# IDE_44m_to_44m.net
KiCad netlist of a schematic drawn in Altium Designer
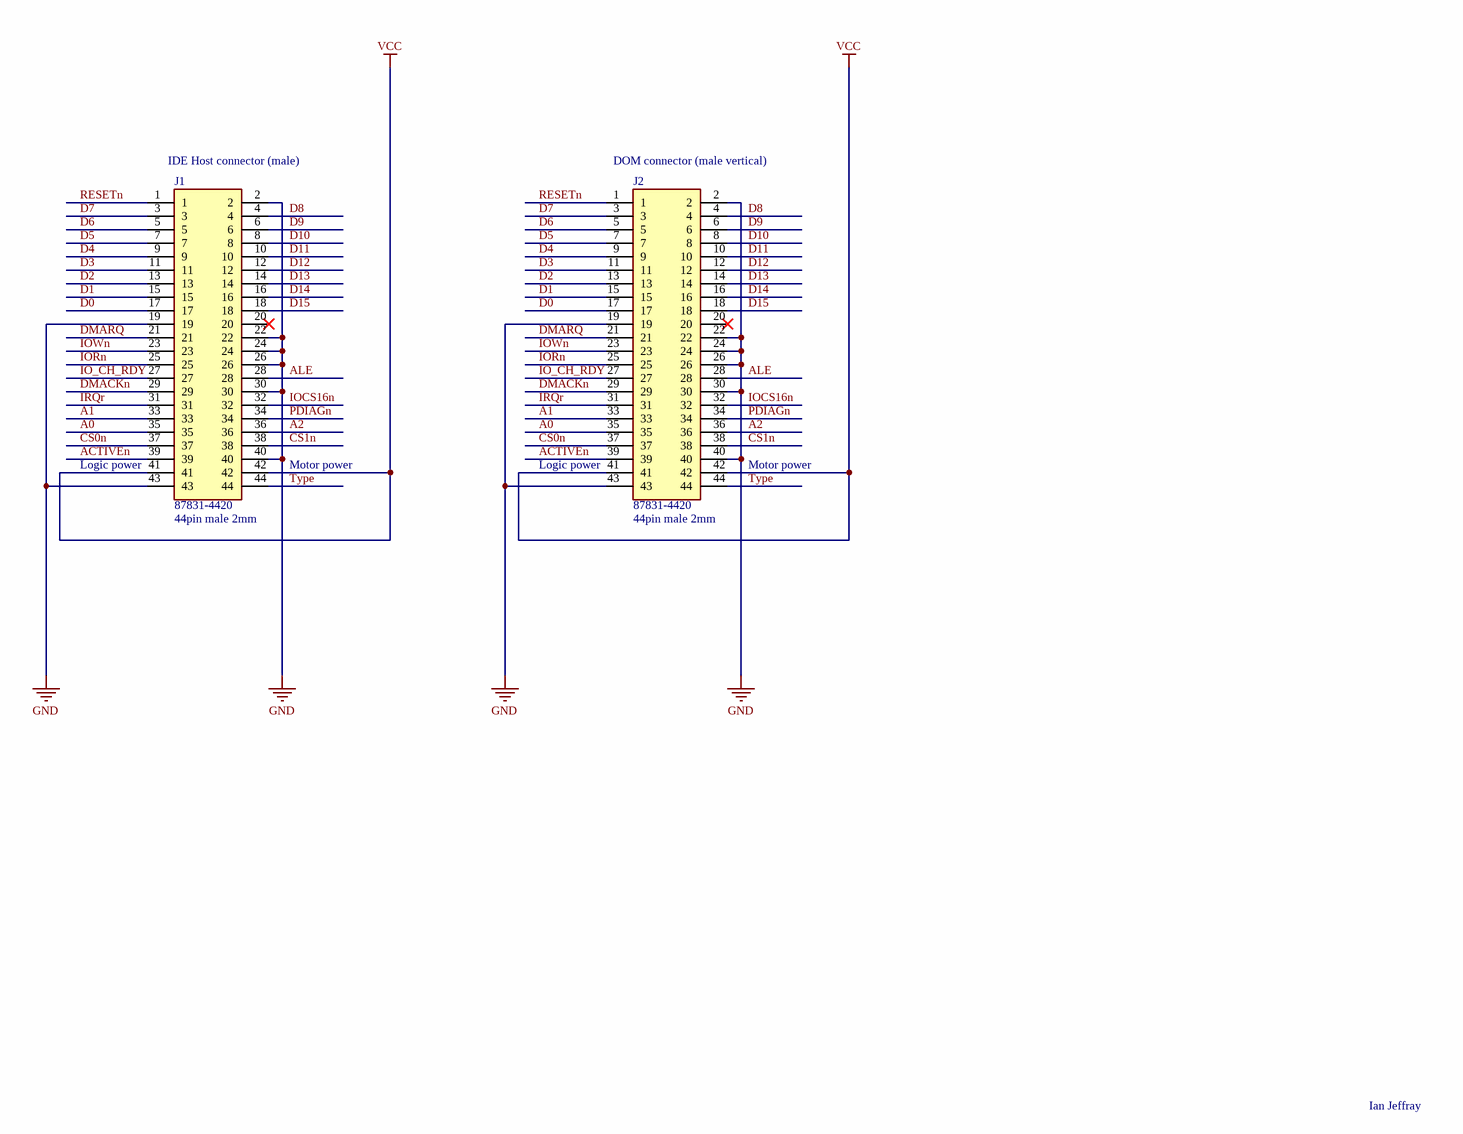
[diagram p0: IDE_44m_to_44m.SchDoc]

(export (version "E")
  (design (tool "Eeschema 10.0.6"))
  (components
    (comp (ref "J1")
      (value "87831-4420")
      (footprint "SamacSys:SHDR44W55P200_2X22_4665X630X640P")
      (description "Drive connector")
      (fields
        (field (name "MOUSER PART NUMBER") "538-87831-4420")
        (field (name "ALTIUM_VALUE") "44pin male 2mm")
      )
      (libsource (lib "*") (part "87831-4420"))
    )
    (comp (ref "J2")
      (value "87831-4420")
      (footprint "SamacSys:SHDR44W55P200_2X22_4665X630X640P")
      (description "Drive connector")
      (fields
        (field (name "MOUSER PART NUMBER") "538-87831-4420")
        (field (name "ALTIUM_VALUE") "44pin male 2mm")
      )
      (libsource (lib "*") (part "87831-4420"))
    )
  )
  (nets
    (net (code "1") (name "/A0") (class "Default")
      (node (ref "J1") (pin "35") (pinfunction "35_35") (pintype "passive"))
      (node (ref "J2") (pin "35") (pinfunction "35_35") (pintype "passive"))
    )
    (net (code "2") (name "/A1") (class "Default")
      (node (ref "J1") (pin "33") (pinfunction "33_33") (pintype "passive"))
      (node (ref "J2") (pin "33") (pinfunction "33_33") (pintype "passive"))
    )
    (net (code "3") (name "/A2") (class "Default")
      (node (ref "J1") (pin "36") (pinfunction "36_36") (pintype "passive"))
      (node (ref "J2") (pin "36") (pinfunction "36_36") (pintype "passive"))
    )
    (net (code "4") (name "/ACTIVEn") (class "Default")
      (node (ref "J1") (pin "39") (pinfunction "39_39") (pintype "passive"))
      (node (ref "J2") (pin "39") (pinfunction "39_39") (pintype "passive"))
    )
    (net (code "5") (name "/ALE") (class "Default")
      (node (ref "J1") (pin "28") (pinfunction "28_28") (pintype "passive"))
      (node (ref "J2") (pin "28") (pinfunction "28_28") (pintype "passive"))
    )
    (net (code "6") (name "/CS0n") (class "Default")
      (node (ref "J1") (pin "37") (pinfunction "37_37") (pintype "passive"))
      (node (ref "J2") (pin "37") (pinfunction "37_37") (pintype "passive"))
    )
    (net (code "7") (name "/CS1n") (class "Default")
      (node (ref "J1") (pin "38") (pinfunction "38_38") (pintype "passive"))
      (node (ref "J2") (pin "38") (pinfunction "38_38") (pintype "passive"))
    )
    (net (code "8") (name "/D0") (class "Default")
      (node (ref "J1") (pin "17") (pinfunction "17_17") (pintype "passive"))
      (node (ref "J2") (pin "17") (pinfunction "17_17") (pintype "passive"))
    )
    (net (code "9") (name "/D1") (class "Default")
      (node (ref "J1") (pin "15") (pinfunction "15_15") (pintype "passive"))
      (node (ref "J2") (pin "15") (pinfunction "15_15") (pintype "passive"))
    )
    (net (code "10") (name "/D2") (class "Default")
      (node (ref "J1") (pin "13") (pinfunction "13_13") (pintype "passive"))
      (node (ref "J2") (pin "13") (pinfunction "13_13") (pintype "passive"))
    )
    (net (code "11") (name "/D3") (class "Default")
      (node (ref "J1") (pin "11") (pinfunction "11_11") (pintype "passive"))
      (node (ref "J2") (pin "11") (pinfunction "11_11") (pintype "passive"))
    )
    (net (code "12") (name "/D4") (class "Default")
      (node (ref "J1") (pin "9") (pinfunction "9_9") (pintype "passive"))
      (node (ref "J2") (pin "9") (pinfunction "9_9") (pintype "passive"))
    )
    (net (code "13") (name "/D5") (class "Default")
      (node (ref "J1") (pin "7") (pinfunction "7_7") (pintype "passive"))
      (node (ref "J2") (pin "7") (pinfunction "7_7") (pintype "passive"))
    )
    (net (code "14") (name "/D6") (class "Default")
      (node (ref "J1") (pin "5") (pinfunction "5_5") (pintype "passive"))
      (node (ref "J2") (pin "5") (pinfunction "5_5") (pintype "passive"))
    )
    (net (code "15") (name "/D7") (class "Default")
      (node (ref "J1") (pin "3") (pinfunction "3_3") (pintype "passive"))
      (node (ref "J2") (pin "3") (pinfunction "3_3") (pintype "passive"))
    )
    (net (code "16") (name "/D8") (class "Default")
      (node (ref "J1") (pin "4") (pinfunction "4_4") (pintype "passive"))
      (node (ref "J2") (pin "4") (pinfunction "4_4") (pintype "passive"))
    )
    (net (code "17") (name "/D9") (class "Default")
      (node (ref "J1") (pin "6") (pinfunction "6_6") (pintype "passive"))
      (node (ref "J2") (pin "6") (pinfunction "6_6") (pintype "passive"))
    )
    (net (code "18") (name "/D10") (class "Default")
      (node (ref "J1") (pin "8") (pinfunction "8_8") (pintype "passive"))
      (node (ref "J2") (pin "8") (pinfunction "8_8") (pintype "passive"))
    )
    (net (code "19") (name "/D11") (class "Default")
      (node (ref "J1") (pin "10") (pinfunction "10_10") (pintype "passive"))
      (node (ref "J2") (pin "10") (pinfunction "10_10") (pintype "passive"))
    )
    (net (code "20") (name "/D12") (class "Default")
      (node (ref "J1") (pin "12") (pinfunction "12_12") (pintype "passive"))
      (node (ref "J2") (pin "12") (pinfunction "12_12") (pintype "passive"))
    )
    (net (code "21") (name "/D13") (class "Default")
      (node (ref "J1") (pin "14") (pinfunction "14_14") (pintype "passive"))
      (node (ref "J2") (pin "14") (pinfunction "14_14") (pintype "passive"))
    )
    (net (code "22") (name "/D14") (class "Default")
      (node (ref "J1") (pin "16") (pinfunction "16_16") (pintype "passive"))
      (node (ref "J2") (pin "16") (pinfunction "16_16") (pintype "passive"))
    )
    (net (code "23") (name "/D15") (class "Default")
      (node (ref "J1") (pin "18") (pinfunction "18_18") (pintype "passive"))
      (node (ref "J2") (pin "18") (pinfunction "18_18") (pintype "passive"))
    )
    (net (code "24") (name "/DMACKn") (class "Default")
      (node (ref "J1") (pin "29") (pinfunction "29_29") (pintype "passive"))
      (node (ref "J2") (pin "29") (pinfunction "29_29") (pintype "passive"))
    )
    (net (code "25") (name "/DMARQ") (class "Default")
      (node (ref "J1") (pin "21") (pinfunction "21_21") (pintype "passive"))
      (node (ref "J2") (pin "21") (pinfunction "21_21") (pintype "passive"))
    )
    (net (code "26") (name "/IOCS16n") (class "Default")
      (node (ref "J1") (pin "32") (pinfunction "32_32") (pintype "passive"))
      (node (ref "J2") (pin "32") (pinfunction "32_32") (pintype "passive"))
    )
    (net (code "27") (name "/IORn") (class "Default")
      (node (ref "J1") (pin "25") (pinfunction "25_25") (pintype "passive"))
      (node (ref "J2") (pin "25") (pinfunction "25_25") (pintype "passive"))
    )
    (net (code "28") (name "/IOWn") (class "Default")
      (node (ref "J1") (pin "23") (pinfunction "23_23") (pintype "passive"))
      (node (ref "J2") (pin "23") (pinfunction "23_23") (pintype "passive"))
    )
    (net (code "29") (name "/IO_CH_RDY") (class "Default")
      (node (ref "J1") (pin "27") (pinfunction "27_27") (pintype "passive"))
      (node (ref "J2") (pin "27") (pinfunction "27_27") (pintype "passive"))
    )
    (net (code "30") (name "/IRQr") (class "Default")
      (node (ref "J1") (pin "31") (pinfunction "31_31") (pintype "passive"))
      (node (ref "J2") (pin "31") (pinfunction "31_31") (pintype "passive"))
    )
    (net (code "31") (name "/PDIAGn") (class "Default")
      (node (ref "J1") (pin "34") (pinfunction "34_34") (pintype "passive"))
      (node (ref "J2") (pin "34") (pinfunction "34_34") (pintype "passive"))
    )
    (net (code "32") (name "/RESETn") (class "Default")
      (node (ref "J1") (pin "1") (pinfunction "1_1") (pintype "passive"))
      (node (ref "J2") (pin "1") (pinfunction "1_1") (pintype "passive"))
    )
    (net (code "33") (name "/Type") (class "Default")
      (node (ref "J1") (pin "44") (pinfunction "44_44") (pintype "passive"))
      (node (ref "J2") (pin "44") (pinfunction "44_44") (pintype "passive"))
    )
    (net (code "34") (name "GND") (class "Default")
      (node (ref "J1") (pin "19") (pinfunction "19_19") (pintype "passive"))
      (node (ref "J1") (pin "2") (pinfunction "2_2") (pintype "passive"))
      (node (ref "J1") (pin "22") (pinfunction "22_22") (pintype "passive"))
      (node (ref "J1") (pin "24") (pinfunction "24_24") (pintype "passive"))
      (node (ref "J1") (pin "26") (pinfunction "26_26") (pintype "passive"))
      (node (ref "J1") (pin "30") (pinfunction "30_30") (pintype "passive"))
      (node (ref "J1") (pin "40") (pinfunction "40_40") (pintype "passive"))
      (node (ref "J1") (pin "43") (pinfunction "43_43") (pintype "passive"))
      (node (ref "J2") (pin "19") (pinfunction "19_19") (pintype "passive"))
      (node (ref "J2") (pin "2") (pinfunction "2_2") (pintype "passive"))
      (node (ref "J2") (pin "22") (pinfunction "22_22") (pintype "passive"))
      (node (ref "J2") (pin "24") (pinfunction "24_24") (pintype "passive"))
      (node (ref "J2") (pin "26") (pinfunction "26_26") (pintype "passive"))
      (node (ref "J2") (pin "30") (pinfunction "30_30") (pintype "passive"))
      (node (ref "J2") (pin "40") (pinfunction "40_40") (pintype "passive"))
      (node (ref "J2") (pin "43") (pinfunction "43_43") (pintype "passive"))
    )
    (net (code "35") (name "VCC") (class "Default")
      (node (ref "J1") (pin "41") (pinfunction "41_41") (pintype "passive"))
      (node (ref "J1") (pin "42") (pinfunction "42_42") (pintype "passive"))
      (node (ref "J2") (pin "41") (pinfunction "41_41") (pintype "passive"))
      (node (ref "J2") (pin "42") (pinfunction "42_42") (pintype "passive"))
    )
    (net (code "36") (name "unconnected-(J1-Pad20)") (class "Default")
      (node (ref "J1") (pin "20") (pinfunction "20_20") (pintype "passive+no_connect"))
    )
    (net (code "37") (name "unconnected-(J2-Pad20)") (class "Default")
      (node (ref "J2") (pin "20") (pinfunction "20_20") (pintype "passive+no_connect"))
    )
  )
)
